# uno.net
KiCad netlist of a schematic drawn in EAGLE
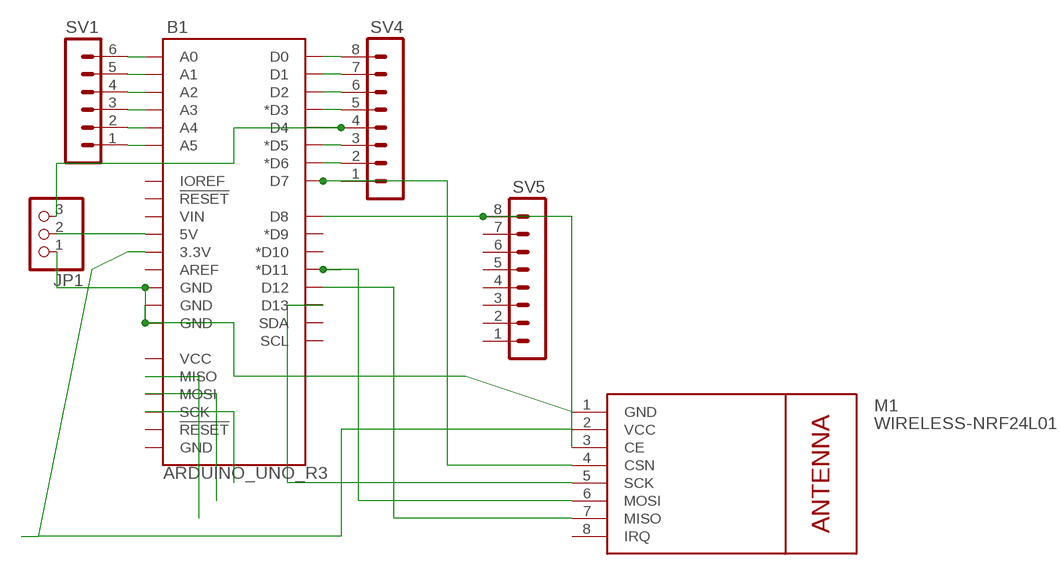
[diagram p0: schematic, sheet 1]

(export (version "E")
  (design (tool "Eeschema 10.0.6"))
  (components
    (comp (ref "B1")
      (value "ARDUINO_UNO_R3")
      (footprint "eagle-import:ARDUINO_R3")
      (libsource (lib "eagle-import") (part "ARDUINO_UNO_R3"))
    )
    (comp (ref "JP1")
      (value "PINHD-1X3")
      (footprint "eagle-import:1X03")
      (libsource (lib "eagle-import") (part "PINHD-1X3"))
    )
    (comp (ref "M1")
      (value "WIRELESS-NRF24L01")
      (footprint "eagle-import:WIRELESS-NRF24L01")
      (libsource (lib "eagle-import") (part "WIRELESS-NRF24L01"))
    )
    (comp (ref "SV1")
      (value "MA06-1")
      (footprint "eagle-import:MA06-1")
      (libsource (lib "eagle-import") (part "MA06-1"))
    )
    (comp (ref "SV4")
      (value "MA08-1")
      (footprint "eagle-import:MA08-1")
      (libsource (lib "eagle-import") (part "MA08-1"))
    )
    (comp (ref "SV5")
      (value "MA08-1")
      (footprint "eagle-import:MA08-1")
      (libsource (lib "eagle-import") (part "MA08-1"))
    )
  )
  (nets
    (net (code "1") (name "Net-(B1-*D3)") (class "Default")
      (node (ref "B1") (pin "D3") (pinfunction "*D3_D3") (pintype "bidirectional"))
      (node (ref "SV4") (pin "5") (pinfunction "5_5") (pintype "passive"))
    )
    (net (code "2") (name "Net-(B1-*D5)") (class "Default")
      (node (ref "B1") (pin "D5") (pinfunction "*D5_D5") (pintype "bidirectional"))
      (node (ref "SV4") (pin "3") (pinfunction "3_3") (pintype "passive"))
    )
    (net (code "3") (name "Net-(B1-*D6)") (class "Default")
      (node (ref "B1") (pin "D6") (pinfunction "*D6_D6") (pintype "bidirectional"))
      (node (ref "SV4") (pin "2") (pinfunction "2_2") (pintype "passive"))
    )
    (net (code "4") (name "Net-(B1-*D11)") (class "Default")
      (node (ref "B1") (pin "D11") (pinfunction "*D11_D11") (pintype "bidirectional"))
      (node (ref "M1") (pin "6") (pinfunction "MOSI_6") (pintype "bidirectional"))
    )
    (net (code "5") (name "Net-(B1-Pad5V)") (class "Default")
      (node (ref "B1") (pin "5V") (pinfunction "5V_5V") (pintype "bidirectional"))
      (node (ref "JP1") (pin "2") (pinfunction "2_2") (pintype "passive"))
    )
    (net (code "6") (name "Net-(B1-PadA0)") (class "Default")
      (node (ref "B1") (pin "A0") (pinfunction "A0_A0") (pintype "bidirectional"))
      (node (ref "SV1") (pin "6") (pinfunction "6_6") (pintype "passive"))
    )
    (net (code "7") (name "Net-(B1-PadA1)") (class "Default")
      (node (ref "B1") (pin "A1") (pinfunction "A1_A1") (pintype "bidirectional"))
      (node (ref "SV1") (pin "5") (pinfunction "5_5") (pintype "passive"))
    )
    (net (code "8") (name "Net-(B1-PadA2)") (class "Default")
      (node (ref "B1") (pin "A2") (pinfunction "A2_A2") (pintype "bidirectional"))
      (node (ref "SV1") (pin "4") (pinfunction "4_4") (pintype "passive"))
    )
    (net (code "9") (name "Net-(B1-PadA3)") (class "Default")
      (node (ref "B1") (pin "A3") (pinfunction "A3_A3") (pintype "bidirectional"))
      (node (ref "SV1") (pin "3") (pinfunction "3_3") (pintype "passive"))
    )
    (net (code "10") (name "Net-(B1-PadA4)") (class "Default")
      (node (ref "B1") (pin "A4") (pinfunction "A4_A4") (pintype "bidirectional"))
      (node (ref "SV1") (pin "2") (pinfunction "2_2") (pintype "passive"))
    )
    (net (code "11") (name "Net-(B1-PadA5)") (class "Default")
      (node (ref "B1") (pin "A5") (pinfunction "A5_A5") (pintype "bidirectional"))
      (node (ref "SV1") (pin "1") (pinfunction "1_1") (pintype "passive"))
    )
    (net (code "12") (name "Net-(B1-PadD0)") (class "Default")
      (node (ref "B1") (pin "D0") (pinfunction "D0_D0") (pintype "bidirectional"))
      (node (ref "SV4") (pin "8") (pinfunction "8_8") (pintype "passive"))
    )
    (net (code "13") (name "Net-(B1-PadD1)") (class "Default")
      (node (ref "B1") (pin "D1") (pinfunction "D1_D1") (pintype "bidirectional"))
      (node (ref "SV4") (pin "7") (pinfunction "7_7") (pintype "passive"))
    )
    (net (code "14") (name "Net-(B1-PadD2)") (class "Default")
      (node (ref "B1") (pin "D2") (pinfunction "D2_D2") (pintype "bidirectional"))
      (node (ref "SV4") (pin "6") (pinfunction "6_6") (pintype "passive"))
    )
    (net (code "15") (name "Net-(B1-PadD4)") (class "Default")
      (node (ref "B1") (pin "D4") (pinfunction "D4_D4") (pintype "bidirectional"))
      (node (ref "JP1") (pin "3") (pinfunction "3_3") (pintype "passive"))
      (node (ref "SV4") (pin "4") (pinfunction "4_4") (pintype "passive"))
    )
    (net (code "16") (name "Net-(M1-CE)") (class "Default")
      (node (ref "B1") (pin "D8") (pinfunction "D8_D8") (pintype "bidirectional"))
      (node (ref "M1") (pin "3") (pinfunction "CE_3") (pintype "bidirectional"))
      (node (ref "SV5") (pin "8") (pinfunction "8_8") (pintype "passive"))
    )
    (net (code "17") (name "Net-(M1-CSN)") (class "Default")
      (node (ref "B1") (pin "D7") (pinfunction "D7_D7") (pintype "bidirectional"))
      (node (ref "M1") (pin "4") (pinfunction "CSN_4") (pintype "bidirectional"))
      (node (ref "SV4") (pin "1") (pinfunction "1_1") (pintype "passive"))
    )
    (net (code "18") (name "Net-(M1-GND)") (class "Default")
      (node (ref "B1") (pin "GND@2") (pinfunction "GND_GND@2") (pintype "bidirectional"))
      (node (ref "B1") (pin "GND@3") (pinfunction "GND_GND@3") (pintype "bidirectional"))
      (node (ref "B1") (pin "GND@4") (pinfunction "GND_GND@4") (pintype "bidirectional"))
      (node (ref "JP1") (pin "1") (pinfunction "1_1") (pintype "passive"))
      (node (ref "M1") (pin "1") (pinfunction "GND_1") (pintype "power_in"))
    )
    (net (code "19") (name "Net-(M1-MISO)") (class "Default")
      (node (ref "B1") (pin "D12") (pinfunction "D12_D12") (pintype "bidirectional"))
      (node (ref "M1") (pin "7") (pinfunction "MISO_7") (pintype "bidirectional"))
    )
    (net (code "20") (name "Net-(M1-SCK)") (class "Default")
      (node (ref "B1") (pin "D13") (pinfunction "D13_D13") (pintype "bidirectional"))
      (node (ref "M1") (pin "5") (pinfunction "SCK_5") (pintype "bidirectional"))
    )
    (net (code "21") (name "Net-(M1-VCC)") (class "Default")
      (node (ref "B1") (pin "3.3V") (pinfunction "3.3V_3.3V") (pintype "bidirectional"))
      (node (ref "M1") (pin "2") (pinfunction "VCC_2") (pintype "power_in"))
    )
    (net (code "22") (name "unconnected-(B1-*D9-PadD9)") (class "Default")
      (node (ref "B1") (pin "D9") (pinfunction "*D9_D9") (pintype "bidirectional"))
    )
    (net (code "23") (name "unconnected-(B1-*D10-PadD10)") (class "Default")
      (node (ref "B1") (pin "D10") (pinfunction "*D10_D10") (pintype "bidirectional"))
    )
    (net (code "24") (name "unconnected-(B1-GND-PadGND@1)") (class "Default")
      (node (ref "B1") (pin "GND@1") (pinfunction "GND_GND@1") (pintype "bidirectional"))
    )
    (net (code "25") (name "unconnected-(B1-PadAREF)") (class "Default")
      (node (ref "B1") (pin "AREF") (pinfunction "AREF_AREF") (pintype "bidirectional"))
    )
    (net (code "26") (name "unconnected-(B1-PadIOREF)") (class "Default")
      (node (ref "B1") (pin "IOREF") (pinfunction "IOREF_IOREF") (pintype "bidirectional"))
    )
    (net (code "27") (name "unconnected-(B1-PadMISO)") (class "Default")
      (node (ref "B1") (pin "MISO") (pinfunction "MISO_MISO") (pintype "bidirectional"))
    )
    (net (code "28") (name "unconnected-(B1-PadMOSI)") (class "Default")
      (node (ref "B1") (pin "MOSI") (pinfunction "MOSI_MOSI") (pintype "bidirectional"))
    )
    (net (code "29") (name "unconnected-(B1-PadSCK)") (class "Default")
      (node (ref "B1") (pin "SCK") (pinfunction "SCK_SCK") (pintype "bidirectional"))
    )
    (net (code "30") (name "unconnected-(B1-PadSCL)") (class "Default")
      (node (ref "B1") (pin "SCL") (pinfunction "SCL_SCL") (pintype "bidirectional"))
    )
    (net (code "31") (name "unconnected-(B1-PadSDA)") (class "Default")
      (node (ref "B1") (pin "SDA") (pinfunction "SDA_SDA") (pintype "bidirectional"))
    )
    (net (code "32") (name "unconnected-(B1-PadVCC)") (class "Default")
      (node (ref "B1") (pin "VCC") (pinfunction "VCC_VCC") (pintype "bidirectional"))
    )
    (net (code "33") (name "unconnected-(B1-PadVIN)") (class "Default")
      (node (ref "B1") (pin "VIN") (pinfunction "VIN_VIN") (pintype "bidirectional"))
    )
    (net (code "34") (name "unconnected-(B1-~{RESET}-PadRESET@1)") (class "Default")
      (node (ref "B1") (pin "RESET@1") (pinfunction "~{RESET}_RESET@1") (pintype "bidirectional"))
    )
    (net (code "35") (name "unconnected-(B1-~{RESET}-PadRESET@2)") (class "Default")
      (node (ref "B1") (pin "RESET@2") (pinfunction "~{RESET}_RESET@2") (pintype "bidirectional"))
    )
    (net (code "36") (name "unconnected-(M1-IRQ-Pad8)") (class "Default")
      (node (ref "M1") (pin "8") (pinfunction "IRQ_8") (pintype "bidirectional"))
    )
    (net (code "37") (name "unconnected-(SV5-Pad1)") (class "Default")
      (node (ref "SV5") (pin "1") (pinfunction "1_1") (pintype "passive"))
    )
    (net (code "38") (name "unconnected-(SV5-Pad2)") (class "Default")
      (node (ref "SV5") (pin "2") (pinfunction "2_2") (pintype "passive"))
    )
    (net (code "39") (name "unconnected-(SV5-Pad3)") (class "Default")
      (node (ref "SV5") (pin "3") (pinfunction "3_3") (pintype "passive"))
    )
    (net (code "40") (name "unconnected-(SV5-Pad4)") (class "Default")
      (node (ref "SV5") (pin "4") (pinfunction "4_4") (pintype "passive"))
    )
    (net (code "41") (name "unconnected-(SV5-Pad5)") (class "Default")
      (node (ref "SV5") (pin "5") (pinfunction "5_5") (pintype "passive"))
    )
    (net (code "42") (name "unconnected-(SV5-Pad6)") (class "Default")
      (node (ref "SV5") (pin "6") (pinfunction "6_6") (pintype "passive"))
    )
    (net (code "43") (name "unconnected-(SV5-Pad7)") (class "Default")
      (node (ref "SV5") (pin "7") (pinfunction "7_7") (pintype "passive"))
    )
  )
)
